# RS485_Channel_2.net
KiCad netlist of a schematic drawn in Altium Designer
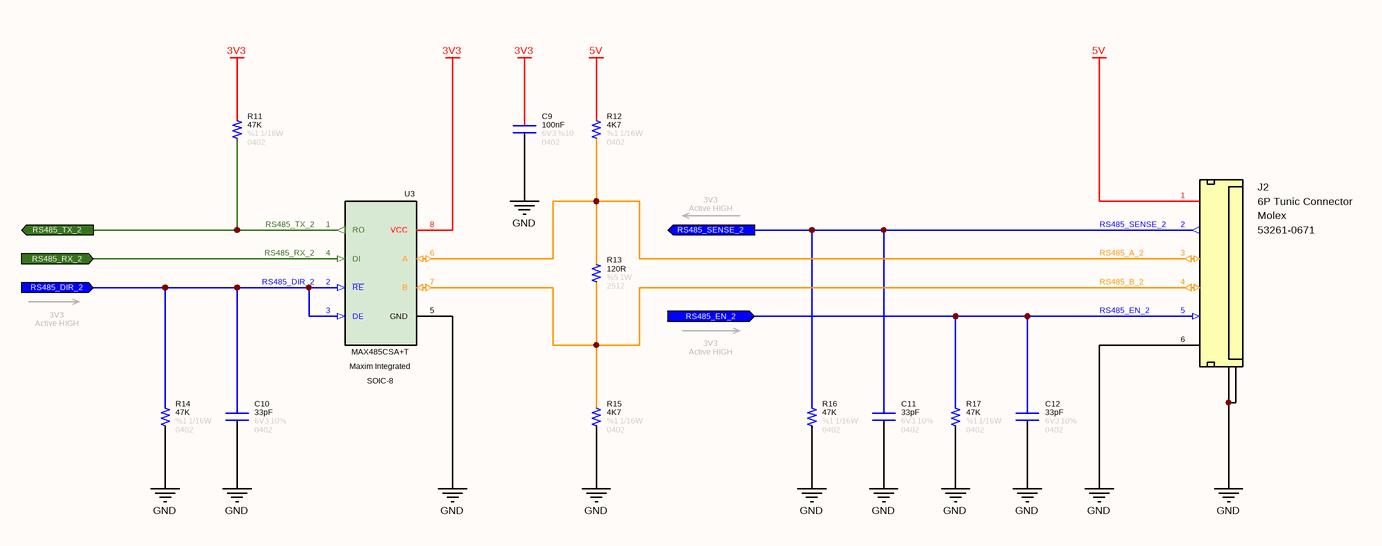
[diagram p0: RS485 Channel 2.SchDoc]

(export (version "E")
  (design (tool "Eeschema 10.0.6"))
  (components
    (comp (ref "C9")
      (value "100nF")
      (footprint "CAPACITOR_0402")
      (description "Capacitor - 100nF [0402-6V3] (Ceramic)")
      (fields
        (field (name "MANUFACTURER PART NUMBER") "04026D104KAT4A")
        (field (name "TOLERANCE") "%10")
        (field (name "VOLTAGE") "6V3")
        (field (name "CASE") "0402")
        (field (name "Comment") "Capacitor - 100nF [0402] (Ceramic)")
      )
      (libsource (lib "Akkoyun") (part "Capacitor - 100nF [0402-6V3]"))
    )
    (comp (ref "C10")
      (value "33pF")
      (footprint "CAPACITOR_0402")
      (description "Capacitor - 33pF [0402] (Ceramic)")
      (fields
        (field (name "MANUFACTURER PART NUMBER") "C0402C330J9RACAUTO")
        (field (name "TOLERANCE") "10%")
        (field (name "CASE") "0402")
        (field (name "VOLTAGE") "6V3")
      )
      (libsource (lib "Akkoyun") (part "Capacitor - 33pF [0402-6V3]"))
    )
    (comp (ref "C11")
      (value "33pF")
      (footprint "CAPACITOR_0402")
      (description "Capacitor - 33pF [0402] (Ceramic)")
      (fields
        (field (name "MANUFACTURER PART NUMBER") "C0402C330J9RACAUTO")
        (field (name "TOLERANCE") "10%")
        (field (name "CASE") "0402")
        (field (name "VOLTAGE") "6V3")
      )
      (libsource (lib "Akkoyun") (part "Capacitor - 33pF [0402-6V3]"))
    )
    (comp (ref "C12")
      (value "33pF")
      (footprint "CAPACITOR_0402")
      (description "Capacitor - 33pF [0402] (Ceramic)")
      (fields
        (field (name "MANUFACTURER PART NUMBER") "C0402C330J9RACAUTO")
        (field (name "TOLERANCE") "10%")
        (field (name "CASE") "0402")
        (field (name "VOLTAGE") "6V3")
      )
      (libsource (lib "Akkoyun") (part "Capacitor - 33pF [0402-6V3]"))
    )
    (comp (ref "J2")
      (value "6P Tunic Connector")
      (footprint "Connector_Tunic 6P")
      (description "Mini Tunic Connector with 6P")
      (fields
        (field (name "MANUFACTURER PART NUMBER") "53261-0671")
        (field (name "MANUFACTURER NAME") "Molex")
      )
      (libsource (lib "Akkoyun") (part "Connector - Mini Tunic 6P (1.25)"))
    )
    (comp (ref "R11")
      (value "47K")
      (footprint "RESISTOR_0402")
      (description "Thick Film Resistors - SMD 1/16 W 47 KOhm 1%")
      (fields
        (field (name "MANUFACTURER PART NUMBER") "CRCW040247K0FKED")
        (field (name "TOLERANCE") "%1")
        (field (name "CASE") "0402")
        (field (name "POWER") "1/16W")
        (field (name "Comment") "47K - 0402 - %1 - 1/16W")
      )
      (libsource (lib "Akkoyun") (part "Resistor - 47K [0402]"))
    )
    (comp (ref "R12")
      (value "4K7")
      (footprint "RESISTOR_0402")
      (description "Thick Film Resistors - SMD 1/16 W 4.7 KOhm 1%")
      (fields
        (field (name "MANUFACTURER PART NUMBER") "CRCW04024K70FKED")
        (field (name "TOLERANCE") "%1")
        (field (name "CASE") "0402")
        (field (name "POWER") "1/16W")
        (field (name "Comment") "4K7 - 0402 - %1 - 1/16W")
      )
      (libsource (lib "Akkoyun") (part "Resistor - 4K7 [0402]"))
    )
    (comp (ref "R13")
      (value "120R")
      (footprint "RESISTOR_2512")
      (description "Thick Film Resistors - SMD 1 W 120 Ohm 5%")
      (fields
        (field (name "MANUFACTURER PART NUMBER") "RC2512JK-07120RL")
        (field (name "TOLERANCE") "%5")
        (field (name "CASE") "2512")
        (field (name "POWER") "1W")
        (field (name "Comment") "120R - 2512 - %5 - 1W")
      )
      (libsource (lib "Akkoyun") (part "Resistor - 120R [2512]"))
    )
    (comp (ref "R14")
      (value "47K")
      (footprint "RESISTOR_0402")
      (description "Thick Film Resistors - SMD 1/16 W 47 KOhm 1%")
      (fields
        (field (name "MANUFACTURER PART NUMBER") "CRCW040247K0FKED")
        (field (name "TOLERANCE") "%1")
        (field (name "CASE") "0402")
        (field (name "POWER") "1/16W")
        (field (name "Comment") "47K - 0402 - %1 - 1/16W")
      )
      (libsource (lib "Akkoyun") (part "Resistor - 47K [0402]"))
    )
    (comp (ref "R15")
      (value "4K7")
      (footprint "RESISTOR_0402")
      (description "Thick Film Resistors - SMD 1/16 W 4.7 KOhm 1%")
      (fields
        (field (name "MANUFACTURER PART NUMBER") "CRCW04024K70FKED")
        (field (name "TOLERANCE") "%1")
        (field (name "CASE") "0402")
        (field (name "POWER") "1/16W")
        (field (name "Comment") "4K7 - 0402 - %1 - 1/16W")
      )
      (libsource (lib "Akkoyun") (part "Resistor - 4K7 [0402]"))
    )
    (comp (ref "R16")
      (value "47K")
      (footprint "RESISTOR_0402")
      (description "Thick Film Resistors - SMD 1/16 W 47 KOhm 1%")
      (fields
        (field (name "MANUFACTURER PART NUMBER") "CRCW040247K0FKED")
        (field (name "TOLERANCE") "%1")
        (field (name "CASE") "0402")
        (field (name "POWER") "1/16W")
        (field (name "Comment") "47K - 0402 - %1 - 1/16W")
      )
      (libsource (lib "Akkoyun") (part "Resistor - 47K [0402]"))
    )
    (comp (ref "R17")
      (value "47K")
      (footprint "RESISTOR_0402")
      (description "Thick Film Resistors - SMD 1/16 W 47 KOhm 1%")
      (fields
        (field (name "MANUFACTURER PART NUMBER") "CRCW040247K0FKED")
        (field (name "TOLERANCE") "%1")
        (field (name "CASE") "0402")
        (field (name "POWER") "1/16W")
        (field (name "Comment") "47K - 0402 - %1 - 1/16W")
      )
      (libsource (lib "Akkoyun") (part "Resistor - 47K [0402]"))
    )
    (comp (ref "U3")
      (value "RS485 Modulator")
      (footprint "SOP-8L (AZRS3080E)")
      (description "RS-422/RS-485 Interface IC Low-Power, Slew-Rate-Limited RS-485/RS-422 Transceivers")
      (fields
        (field (name "CASE") "SOIC-8")
        (field (name "MANUFACTURER PART NUMBER") "MAX485CSA+T")
        (field (name "MANUFACTURER NAME") "Maxim Integrated")
      )
      (libsource (lib "Akkoyun") (part "IC - MAX485CSA+T"))
    )
  )
  (nets
    (net (code "1") (name "/RS485_A_2") (class "Default")
      (node (ref "J2") (pin "3") (pinfunction "RS485-A_3") (pintype "bidirectional"))
      (node (ref "R12") (pin "1") (pinfunction "1_1") (pintype "passive"))
      (node (ref "R13") (pin "2") (pinfunction "2_2") (pintype "passive"))
      (node (ref "U3") (pin "6") (pinfunction "A_6") (pintype "bidirectional"))
    )
    (net (code "2") (name "/RS485_B_2") (class "Default")
      (node (ref "J2") (pin "4") (pinfunction "RS485-B_4") (pintype "bidirectional"))
      (node (ref "R13") (pin "1") (pinfunction "1_1") (pintype "passive"))
      (node (ref "R15") (pin "2") (pinfunction "2_2") (pintype "passive"))
      (node (ref "U3") (pin "7") (pinfunction "B_7") (pintype "bidirectional"))
    )
    (net (code "3") (name "/RS485_DIR_2") (class "Default")
      (node (ref "C10") (pin "2") (pinfunction "2_2") (pintype "passive"))
      (node (ref "R14") (pin "2") (pinfunction "2_2") (pintype "passive"))
      (node (ref "U3") (pin "2") (pinfunction "~{RE}_2") (pintype "input"))
      (node (ref "U3") (pin "3") (pinfunction "DE_3") (pintype "input"))
    )
    (net (code "4") (name "/RS485_EN_2") (class "Default")
      (node (ref "C12") (pin "2") (pinfunction "2_2") (pintype "passive"))
      (node (ref "J2") (pin "5") (pinfunction "INT_5") (pintype "input"))
      (node (ref "R17") (pin "2") (pinfunction "2_2") (pintype "passive"))
    )
    (net (code "5") (name "/RS485_RX_2") (class "Default")
      (node (ref "U3") (pin "4") (pinfunction "DI_4") (pintype "input"))
    )
    (net (code "6") (name "/RS485_SENSE_2") (class "Default")
      (node (ref "C11") (pin "2") (pinfunction "2_2") (pintype "passive"))
      (node (ref "J2") (pin "2") (pinfunction "Sense_2") (pintype "output"))
      (node (ref "R16") (pin "2") (pinfunction "2_2") (pintype "passive"))
    )
    (net (code "7") (name "/RS485_TX_2") (class "Default")
      (node (ref "R11") (pin "1") (pinfunction "1_1") (pintype "passive"))
      (node (ref "U3") (pin "1") (pinfunction "RO_1") (pintype "output"))
    )
    (net (code "8") (name "3V3") (class "Default")
      (node (ref "C9") (pin "2") (pinfunction "2_2") (pintype "passive"))
      (node (ref "R11") (pin "2") (pinfunction "2_2") (pintype "passive"))
      (node (ref "U3") (pin "8") (pinfunction "VCC_8") (pintype "power_in"))
    )
    (net (code "9") (name "5V") (class "Default")
      (node (ref "J2") (pin "1") (pinfunction "5V_1") (pintype "power_in"))
      (node (ref "R12") (pin "2") (pinfunction "2_2") (pintype "passive"))
    )
    (net (code "10") (name "GND") (class "Default")
      (node (ref "C10") (pin "1") (pinfunction "1_1") (pintype "passive"))
      (node (ref "C11") (pin "1") (pinfunction "1_1") (pintype "passive"))
      (node (ref "C12") (pin "1") (pinfunction "1_1") (pintype "passive"))
      (node (ref "C9") (pin "1") (pinfunction "1_1") (pintype "passive"))
      (node (ref "J2") (pin "6") (pinfunction "GND_6") (pintype "power_in"))
      (node (ref "J2") (pin "7") (pinfunction "GND_7") (pintype "passive"))
      (node (ref "J2") (pin "8") (pinfunction "GND_8") (pintype "passive"))
      (node (ref "R14") (pin "1") (pinfunction "1_1") (pintype "passive"))
      (node (ref "R15") (pin "1") (pinfunction "1_1") (pintype "passive"))
      (node (ref "R16") (pin "1") (pinfunction "1_1") (pintype "passive"))
      (node (ref "R17") (pin "1") (pinfunction "1_1") (pintype "passive"))
      (node (ref "U3") (pin "5") (pinfunction "GND_5") (pintype "passive"))
    )
  )
)
